# Status_board.net
KiCad netlist of a schematic drawn in Altium Designer
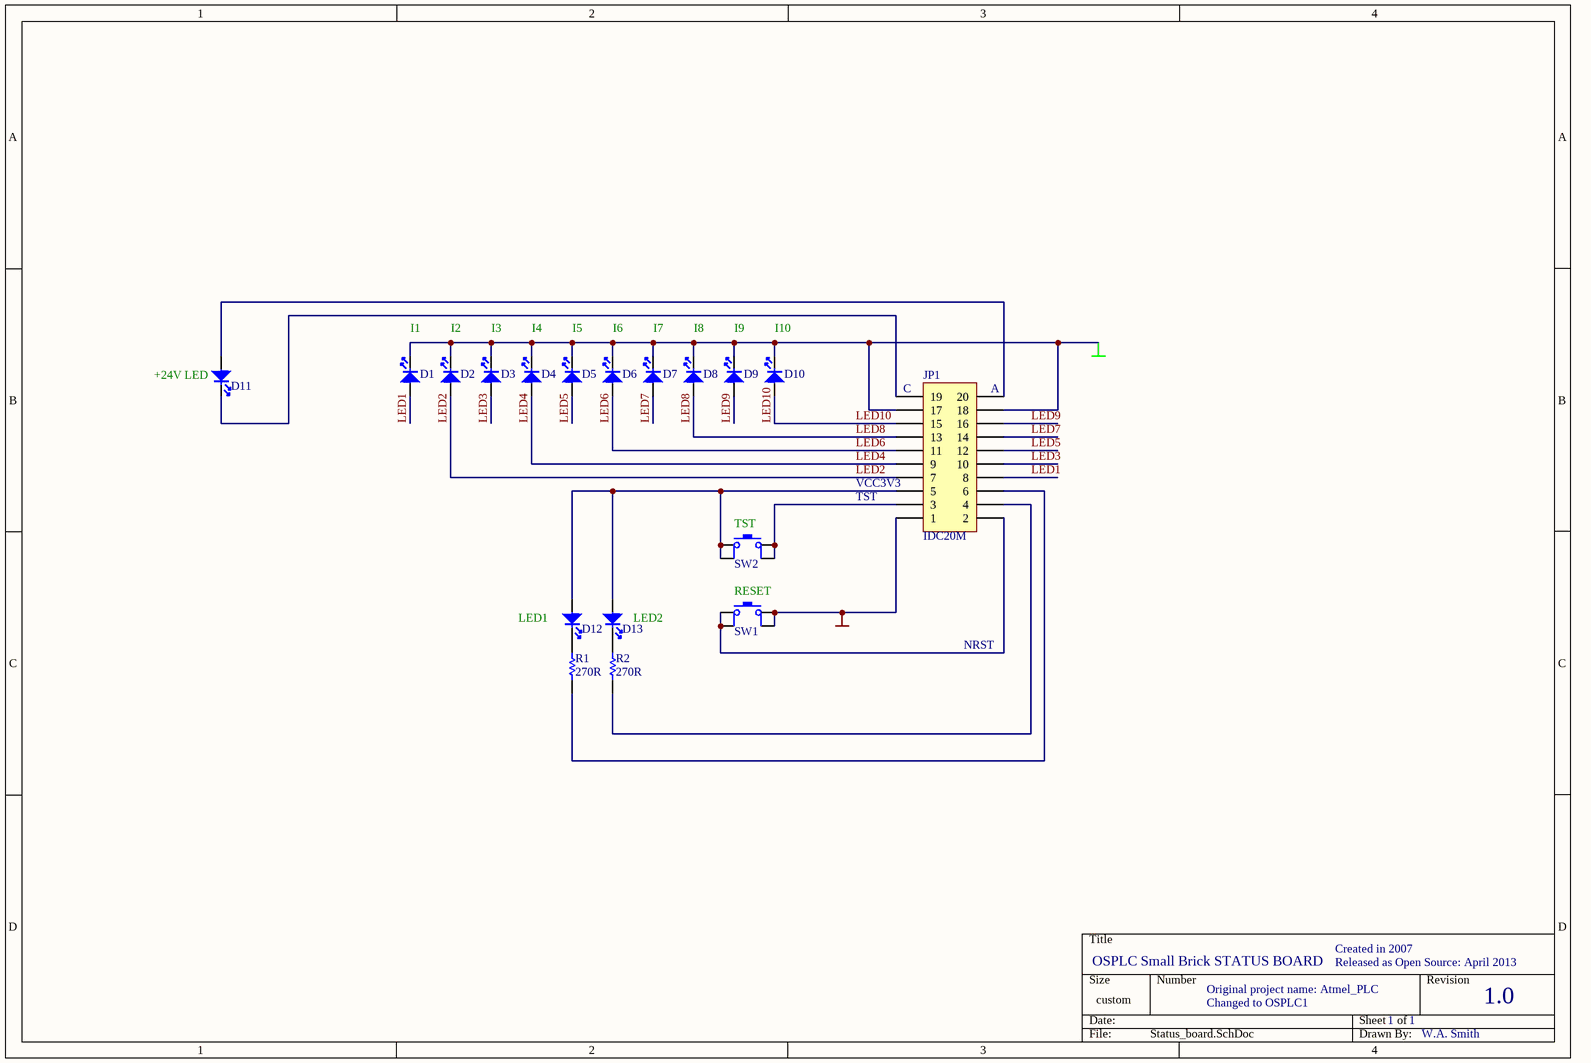
[diagram p0: Status_board.SchDoc]

(export (version "E")
  (design (tool "Eeschema 10.0.6"))
  (components
    (comp (ref "D1")
      (value "LED")
      (footprint "1206_LED")
      (description "1206 footpring LED")
      (libsource (lib "Integrated Comp_lib") (part "LED_1206"))
    )
    (comp (ref "D2")
      (value "LED")
      (footprint "1206_LED")
      (description "1206 footpring LED")
      (libsource (lib "Integrated Comp_lib") (part "LED_1206"))
    )
    (comp (ref "D3")
      (value "LED")
      (footprint "1206_LED")
      (description "1206 footpring LED")
      (libsource (lib "Integrated Comp_lib") (part "LED_1206"))
    )
    (comp (ref "D4")
      (value "LED")
      (footprint "1206_LED")
      (description "1206 footpring LED")
      (libsource (lib "Integrated Comp_lib") (part "LED_1206"))
    )
    (comp (ref "D5")
      (value "LED")
      (footprint "1206_LED")
      (description "1206 footpring LED")
      (libsource (lib "Integrated Comp_lib") (part "LED_1206"))
    )
    (comp (ref "D6")
      (value "LED")
      (footprint "1206_LED")
      (description "1206 footpring LED")
      (libsource (lib "Integrated Comp_lib") (part "LED_1206"))
    )
    (comp (ref "D7")
      (value "LED")
      (footprint "1206_LED")
      (description "1206 footpring LED")
      (libsource (lib "Integrated Comp_lib") (part "LED_1206"))
    )
    (comp (ref "D8")
      (value "LED")
      (footprint "1206_LED")
      (description "1206 footpring LED")
      (libsource (lib "Integrated Comp_lib") (part "LED_1206"))
    )
    (comp (ref "D9")
      (value "LED")
      (footprint "1206_LED")
      (description "1206 footpring LED")
      (libsource (lib "Integrated Comp_lib") (part "LED_1206"))
    )
    (comp (ref "D10")
      (value "LED")
      (footprint "1206_LED")
      (description "1206 footpring LED")
      (libsource (lib "Integrated Comp_lib") (part "LED_1206"))
    )
    (comp (ref "D11")
      (value "LED")
      (footprint "1206_LED")
      (description "1206 footpring LED")
      (libsource (lib "Integrated Comp_lib") (part "LED_1206"))
    )
    (comp (ref "D12")
      (value "LED")
      (footprint "1206_LED")
      (description "1206 footpring LED")
      (libsource (lib "Integrated Comp_lib") (part "LED_1206"))
    )
    (comp (ref "D13")
      (value "LED")
      (footprint "1206_LED")
      (description "1206 footpring LED")
      (libsource (lib "Integrated Comp_lib") (part "LED_1206"))
    )
    (comp (ref "JP1")
      (value "IDC20M")
      (footprint "IDC_20M_BOX")
      (description "20 pin IDC male connector, vertical, box")
      (libsource (lib "ARM_projects") (part "IDC_20M"))
    )
    (comp (ref "R1")
      (value "0805")
      (footprint "0805")
      (description "0805 footprint resistor")
      (fields (field (name "ALTIUM_VALUE") "270R"))
      (libsource (lib "Integrated Comp_lib") (part "RES_0805"))
    )
    (comp (ref "R2")
      (value "0805")
      (footprint "0805")
      (description "0805 footprint resistor")
      (fields (field (name "ALTIUM_VALUE") "270R"))
      (libsource (lib "Integrated Comp_lib") (part "RES_0805"))
    )
    (comp (ref "SW1")
      (value "PB_SWITCH_6x6")
      (footprint "PB_SW_6x6")
      (description "Tact Switch 6mm x 6mm")
      (libsource (lib "Integrated Comp_lib") (part "PB_SWITCH_6x6"))
    )
    (comp (ref "SW2")
      (value "PB_SWITCH_6x6")
      (footprint "PB_SW_6x6")
      (description "Tact Switch 6mm x 6mm")
      (libsource (lib "Integrated Comp_lib") (part "PB_SWITCH_6x6"))
    )
  )
  (nets
    (net (code "1") (name "/LED1") (class "Default")
      (node (ref "D1") (pin "1") (pinfunction "1_1") (pintype "passive"))
      (node (ref "JP1") (pin "8") (pinfunction "8_8") (pintype "passive"))
    )
    (net (code "2") (name "/LED2") (class "Default")
      (node (ref "D2") (pin "1") (pinfunction "1_1") (pintype "passive"))
      (node (ref "JP1") (pin "7") (pinfunction "7_7") (pintype "passive"))
    )
    (net (code "3") (name "/LED3") (class "Default")
      (node (ref "D3") (pin "1") (pinfunction "1_1") (pintype "passive"))
      (node (ref "JP1") (pin "10") (pinfunction "10_10") (pintype "passive"))
    )
    (net (code "4") (name "/LED4") (class "Default")
      (node (ref "D4") (pin "1") (pinfunction "1_1") (pintype "passive"))
      (node (ref "JP1") (pin "9") (pinfunction "9_9") (pintype "passive"))
    )
    (net (code "5") (name "/LED5") (class "Default")
      (node (ref "D5") (pin "1") (pinfunction "1_1") (pintype "passive"))
      (node (ref "JP1") (pin "12") (pinfunction "12_12") (pintype "passive"))
    )
    (net (code "6") (name "/LED6") (class "Default")
      (node (ref "D6") (pin "1") (pinfunction "1_1") (pintype "passive"))
      (node (ref "JP1") (pin "11") (pinfunction "11_11") (pintype "passive"))
    )
    (net (code "7") (name "/LED7") (class "Default")
      (node (ref "D7") (pin "1") (pinfunction "1_1") (pintype "passive"))
      (node (ref "JP1") (pin "14") (pinfunction "14_14") (pintype "passive"))
    )
    (net (code "8") (name "/LED8") (class "Default")
      (node (ref "D8") (pin "1") (pinfunction "1_1") (pintype "passive"))
      (node (ref "JP1") (pin "13") (pinfunction "13_13") (pintype "passive"))
    )
    (net (code "9") (name "/LED9") (class "Default")
      (node (ref "D9") (pin "1") (pinfunction "1_1") (pintype "passive"))
      (node (ref "JP1") (pin "16") (pinfunction "16_16") (pintype "passive"))
    )
    (net (code "10") (name "/LED10") (class "Default")
      (node (ref "D10") (pin "1") (pinfunction "1_1") (pintype "passive"))
      (node (ref "JP1") (pin "15") (pinfunction "15_15") (pintype "passive"))
    )
    (net (code "11") (name "GND") (class "Default")
      (node (ref "JP1") (pin "1") (pinfunction "1_1") (pintype "passive"))
      (node (ref "SW1") (pin "3") (pinfunction "3_3") (pintype "passive"))
      (node (ref "SW1") (pin "4") (pinfunction "4_4") (pintype "passive"))
    )
    (net (code "12") (name "IN_GND") (class "Default")
      (node (ref "D1") (pin "2") (pinfunction "2_2") (pintype "passive"))
      (node (ref "D10") (pin "2") (pinfunction "2_2") (pintype "passive"))
      (node (ref "D2") (pin "2") (pinfunction "2_2") (pintype "passive"))
      (node (ref "D3") (pin "2") (pinfunction "2_2") (pintype "passive"))
      (node (ref "D4") (pin "2") (pinfunction "2_2") (pintype "passive"))
      (node (ref "D5") (pin "2") (pinfunction "2_2") (pintype "passive"))
      (node (ref "D6") (pin "2") (pinfunction "2_2") (pintype "passive"))
      (node (ref "D7") (pin "2") (pinfunction "2_2") (pintype "passive"))
      (node (ref "D8") (pin "2") (pinfunction "2_2") (pintype "passive"))
      (node (ref "D9") (pin "2") (pinfunction "2_2") (pintype "passive"))
      (node (ref "JP1") (pin "17") (pinfunction "17_17") (pintype "passive"))
      (node (ref "JP1") (pin "18") (pinfunction "18_18") (pintype "passive"))
    )
    (net (code "13") (name "Net-(D11-Pad1)") (class "Default")
      (node (ref "D11") (pin "1") (pinfunction "1_1") (pintype "passive"))
      (node (ref "JP1") (pin "20") (pinfunction "20_20") (pintype "passive"))
    )
    (net (code "14") (name "Net-(D11-Pad2)") (class "Default")
      (node (ref "D11") (pin "2") (pinfunction "2_2") (pintype "passive"))
      (node (ref "JP1") (pin "19") (pinfunction "19_19") (pintype "passive"))
    )
    (net (code "15") (name "Net-(D12-Pad2)") (class "Default")
      (node (ref "D12") (pin "2") (pinfunction "2_2") (pintype "passive"))
      (node (ref "R1") (pin "2") (pinfunction "2_2") (pintype "passive"))
    )
    (net (code "16") (name "Net-(D13-Pad2)") (class "Default")
      (node (ref "D13") (pin "2") (pinfunction "2_2") (pintype "passive"))
      (node (ref "R2") (pin "2") (pinfunction "2_2") (pintype "passive"))
    )
    (net (code "17") (name "Net-(JP1-Pad3)") (class "Default")
      (node (ref "JP1") (pin "3") (pinfunction "3_3") (pintype "passive"))
      (node (ref "SW2") (pin "3") (pinfunction "3_3") (pintype "passive"))
      (node (ref "SW2") (pin "4") (pinfunction "4_4") (pintype "passive"))
    )
    (net (code "18") (name "Net-(JP1-Pad4)") (class "Default")
      (node (ref "JP1") (pin "4") (pinfunction "4_4") (pintype "passive"))
      (node (ref "R2") (pin "1") (pinfunction "1_1") (pintype "passive"))
    )
    (net (code "19") (name "Net-(JP1-Pad6)") (class "Default")
      (node (ref "JP1") (pin "6") (pinfunction "6_6") (pintype "passive"))
      (node (ref "R1") (pin "1") (pinfunction "1_1") (pintype "passive"))
    )
    (net (code "20") (name "Net-(SW1-SW1)") (class "Default")
      (node (ref "JP1") (pin "2") (pinfunction "2_2") (pintype "passive"))
      (node (ref "SW1") (pin "1") (pinfunction "SW1_1") (pintype "passive"))
      (node (ref "SW1") (pin "2") (pinfunction "SW2_2") (pintype "passive"))
    )
    (net (code "21") (name "Net-(SW2-SW1)") (class "Default")
      (node (ref "D12") (pin "1") (pinfunction "1_1") (pintype "passive"))
      (node (ref "D13") (pin "1") (pinfunction "1_1") (pintype "passive"))
      (node (ref "JP1") (pin "5") (pinfunction "5_5") (pintype "passive"))
      (node (ref "SW2") (pin "1") (pinfunction "SW1_1") (pintype "passive"))
      (node (ref "SW2") (pin "2") (pinfunction "SW2_2") (pintype "passive"))
    )
  )
)
